# Sheet1.net
KiCad netlist of a schematic drawn in Altium Designer
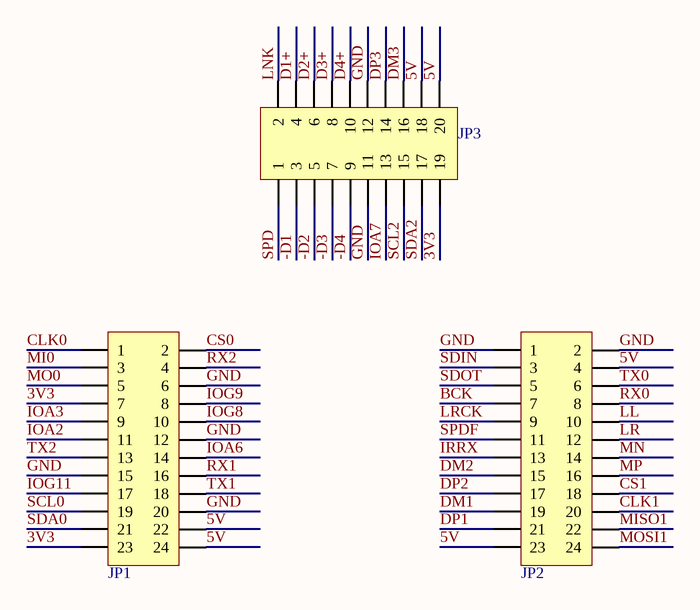
[diagram p0: Sheet1.SchDoc]

(export (version "E")
  (design (tool "Eeschema 10.0.6"))
  (components
    (comp (ref "JP1")
      (value "Header 2X11")
      (footprint "HDR2X12")
      (description "12*2P接插件")
      (fields (field (name "版权归属") "源创客"))
      (libsource (lib "4.5   - 接插件-脚距2.54") (part "Header 12X2"))
    )
    (comp (ref "JP2")
      (value "Header 2X11")
      (footprint "HDR2X12")
      (description "12*2P接插件")
      (fields (field (name "版权归属") "源创客"))
      (libsource (lib "4.5   - 接插件-脚距2.54") (part "Header 12X2"))
    )
    (comp (ref "JP3")
      (value "Header 2X10")
      (footprint "HDR2X10")
      (description "10*2P接插件")
      (fields (field (name "版权归属") "源创客"))
      (libsource (lib "4.5   - 接插件-脚距2.54") (part "Header 10X2"))
    )
  )
  (nets
    (net (code "1") (name "/-D1") (class "Default")
      (node (ref "JP3") (pin "3") (pinfunction "3_3") (pintype "passive"))
    )
    (net (code "2") (name "/-D2") (class "Default")
      (node (ref "JP3") (pin "5") (pinfunction "5_5") (pintype "passive"))
    )
    (net (code "3") (name "/-D3") (class "Default")
      (node (ref "JP3") (pin "7") (pinfunction "7_7") (pintype "passive"))
    )
    (net (code "4") (name "/-D4") (class "Default")
      (node (ref "JP3") (pin "9") (pinfunction "9_9") (pintype "passive"))
    )
    (net (code "5") (name "/3V3") (class "Default")
      (node (ref "JP1") (pin "23") (pinfunction "23_23") (pintype "passive"))
      (node (ref "JP1") (pin "7") (pinfunction "7_7") (pintype "passive"))
      (node (ref "JP3") (pin "19") (pinfunction "19_19") (pintype "passive"))
    )
    (net (code "6") (name "/5V") (class "Default")
      (node (ref "JP1") (pin "22") (pinfunction "22_22") (pintype "passive"))
      (node (ref "JP1") (pin "24") (pinfunction "24_24") (pintype "passive"))
      (node (ref "JP2") (pin "23") (pinfunction "23_23") (pintype "passive"))
      (node (ref "JP2") (pin "4") (pinfunction "4_4") (pintype "passive"))
      (node (ref "JP3") (pin "18") (pinfunction "18_18") (pintype "passive"))
      (node (ref "JP3") (pin "20") (pinfunction "20_20") (pintype "passive"))
    )
    (net (code "7") (name "/BCK") (class "Default")
      (node (ref "JP2") (pin "7") (pinfunction "7_7") (pintype "passive"))
    )
    (net (code "8") (name "/CLK0") (class "Default")
      (node (ref "JP1") (pin "1") (pinfunction "1_1") (pintype "passive"))
    )
    (net (code "9") (name "/CLK1") (class "Default")
      (node (ref "JP2") (pin "20") (pinfunction "20_20") (pintype "passive"))
    )
    (net (code "10") (name "/CS0") (class "Default")
      (node (ref "JP1") (pin "2") (pinfunction "2_2") (pintype "passive"))
    )
    (net (code "11") (name "/CS1") (class "Default")
      (node (ref "JP2") (pin "18") (pinfunction "18_18") (pintype "passive"))
    )
    (net (code "12") (name "/D1+") (class "Default")
      (node (ref "JP3") (pin "4") (pinfunction "4_4") (pintype "passive"))
    )
    (net (code "13") (name "/D2+") (class "Default")
      (node (ref "JP3") (pin "6") (pinfunction "6_6") (pintype "passive"))
    )
    (net (code "14") (name "/D3+") (class "Default")
      (node (ref "JP3") (pin "8") (pinfunction "8_8") (pintype "passive"))
    )
    (net (code "15") (name "/D4+") (class "Default")
      (node (ref "JP3") (pin "10") (pinfunction "10_10") (pintype "passive"))
    )
    (net (code "16") (name "/DM1") (class "Default")
      (node (ref "JP2") (pin "19") (pinfunction "19_19") (pintype "passive"))
    )
    (net (code "17") (name "/DM2") (class "Default")
      (node (ref "JP2") (pin "15") (pinfunction "15_15") (pintype "passive"))
    )
    (net (code "18") (name "/DM3") (class "Default")
      (node (ref "JP3") (pin "16") (pinfunction "16_16") (pintype "passive"))
    )
    (net (code "19") (name "/DP1") (class "Default")
      (node (ref "JP2") (pin "21") (pinfunction "21_21") (pintype "passive"))
    )
    (net (code "20") (name "/DP2") (class "Default")
      (node (ref "JP2") (pin "17") (pinfunction "17_17") (pintype "passive"))
    )
    (net (code "21") (name "/DP3") (class "Default")
      (node (ref "JP3") (pin "14") (pinfunction "14_14") (pintype "passive"))
    )
    (net (code "22") (name "/GND") (class "Default")
      (node (ref "JP1") (pin "12") (pinfunction "12_12") (pintype "passive"))
      (node (ref "JP1") (pin "15") (pinfunction "15_15") (pintype "passive"))
      (node (ref "JP1") (pin "20") (pinfunction "20_20") (pintype "passive"))
      (node (ref "JP1") (pin "6") (pinfunction "6_6") (pintype "passive"))
      (node (ref "JP2") (pin "1") (pinfunction "1_1") (pintype "passive"))
      (node (ref "JP2") (pin "2") (pinfunction "2_2") (pintype "passive"))
      (node (ref "JP3") (pin "11") (pinfunction "11_11") (pintype "passive"))
      (node (ref "JP3") (pin "12") (pinfunction "12_12") (pintype "passive"))
    )
    (net (code "23") (name "/IOA2") (class "Default")
      (node (ref "JP1") (pin "11") (pinfunction "11_11") (pintype "passive"))
    )
    (net (code "24") (name "/IOA3") (class "Default")
      (node (ref "JP1") (pin "9") (pinfunction "9_9") (pintype "passive"))
    )
    (net (code "25") (name "/IOA6") (class "Default")
      (node (ref "JP1") (pin "14") (pinfunction "14_14") (pintype "passive"))
    )
    (net (code "26") (name "/IOA7") (class "Default")
      (node (ref "JP3") (pin "13") (pinfunction "13_13") (pintype "passive"))
    )
    (net (code "27") (name "/IOG8") (class "Default")
      (node (ref "JP1") (pin "10") (pinfunction "10_10") (pintype "passive"))
    )
    (net (code "28") (name "/IOG9") (class "Default")
      (node (ref "JP1") (pin "8") (pinfunction "8_8") (pintype "passive"))
    )
    (net (code "29") (name "/IOG11") (class "Default")
      (node (ref "JP1") (pin "17") (pinfunction "17_17") (pintype "passive"))
    )
    (net (code "30") (name "/IRRX") (class "Default")
      (node (ref "JP2") (pin "13") (pinfunction "13_13") (pintype "passive"))
    )
    (net (code "31") (name "/LL") (class "Default")
      (node (ref "JP2") (pin "10") (pinfunction "10_10") (pintype "passive"))
    )
    (net (code "32") (name "/LNK") (class "Default")
      (node (ref "JP3") (pin "2") (pinfunction "2_2") (pintype "passive"))
    )
    (net (code "33") (name "/LR") (class "Default")
      (node (ref "JP2") (pin "12") (pinfunction "12_12") (pintype "passive"))
    )
    (net (code "34") (name "/LRCK") (class "Default")
      (node (ref "JP2") (pin "9") (pinfunction "9_9") (pintype "passive"))
    )
    (net (code "35") (name "/MI0") (class "Default")
      (node (ref "JP1") (pin "3") (pinfunction "3_3") (pintype "passive"))
    )
    (net (code "36") (name "/MISO1") (class "Default")
      (node (ref "JP2") (pin "22") (pinfunction "22_22") (pintype "passive"))
    )
    (net (code "37") (name "/MN") (class "Default")
      (node (ref "JP2") (pin "14") (pinfunction "14_14") (pintype "passive"))
    )
    (net (code "38") (name "/MO0") (class "Default")
      (node (ref "JP1") (pin "5") (pinfunction "5_5") (pintype "passive"))
    )
    (net (code "39") (name "/MOSI1") (class "Default")
      (node (ref "JP2") (pin "24") (pinfunction "24_24") (pintype "passive"))
    )
    (net (code "40") (name "/MP") (class "Default")
      (node (ref "JP2") (pin "16") (pinfunction "16_16") (pintype "passive"))
    )
    (net (code "41") (name "/RX0") (class "Default")
      (node (ref "JP2") (pin "8") (pinfunction "8_8") (pintype "passive"))
    )
    (net (code "42") (name "/RX1") (class "Default")
      (node (ref "JP1") (pin "16") (pinfunction "16_16") (pintype "passive"))
    )
    (net (code "43") (name "/RX2") (class "Default")
      (node (ref "JP1") (pin "4") (pinfunction "4_4") (pintype "passive"))
    )
    (net (code "44") (name "/SCL0") (class "Default")
      (node (ref "JP1") (pin "19") (pinfunction "19_19") (pintype "passive"))
    )
    (net (code "45") (name "/SCL2") (class "Default")
      (node (ref "JP3") (pin "15") (pinfunction "15_15") (pintype "passive"))
    )
    (net (code "46") (name "/SDA0") (class "Default")
      (node (ref "JP1") (pin "21") (pinfunction "21_21") (pintype "passive"))
    )
    (net (code "47") (name "/SDA2") (class "Default")
      (node (ref "JP3") (pin "17") (pinfunction "17_17") (pintype "passive"))
    )
    (net (code "48") (name "/SDIN") (class "Default")
      (node (ref "JP2") (pin "3") (pinfunction "3_3") (pintype "passive"))
    )
    (net (code "49") (name "/SDOT") (class "Default")
      (node (ref "JP2") (pin "5") (pinfunction "5_5") (pintype "passive"))
    )
    (net (code "50") (name "/SPD") (class "Default")
      (node (ref "JP3") (pin "1") (pinfunction "1_1") (pintype "passive"))
    )
    (net (code "51") (name "/SPDF") (class "Default")
      (node (ref "JP2") (pin "11") (pinfunction "11_11") (pintype "passive"))
    )
    (net (code "52") (name "/TX0") (class "Default")
      (node (ref "JP2") (pin "6") (pinfunction "6_6") (pintype "passive"))
    )
    (net (code "53") (name "/TX1") (class "Default")
      (node (ref "JP1") (pin "18") (pinfunction "18_18") (pintype "passive"))
    )
    (net (code "54") (name "/TX2") (class "Default")
      (node (ref "JP1") (pin "13") (pinfunction "13_13") (pintype "passive"))
    )
  )
)
